# A7105_reference_design.net
KiCad netlist of a schematic drawn in EAGLE
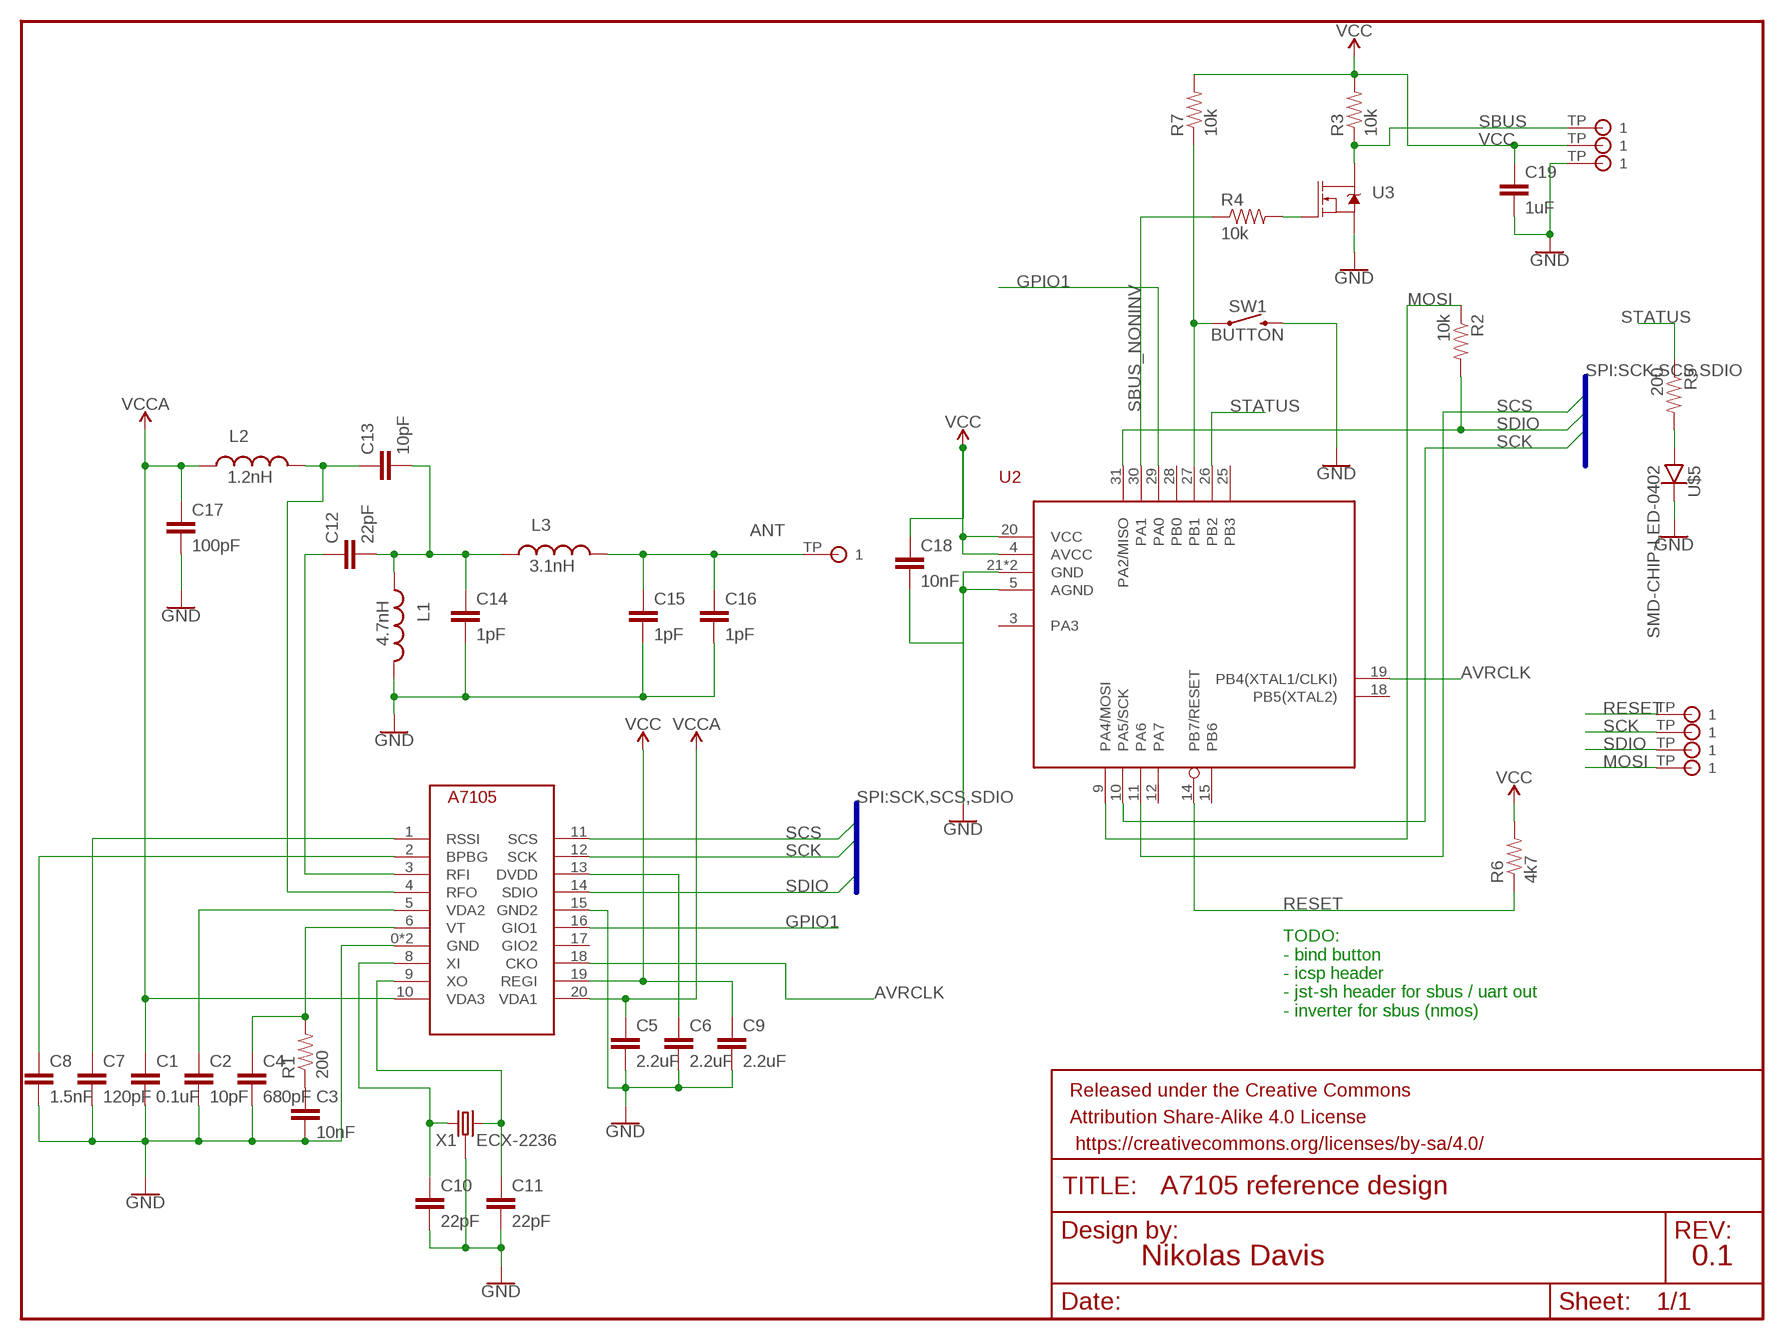
[diagram p0: schematic, sheet 1]

(export (version "E")
  (design (tool "Eeschema 10.0.6"))
  (components
    (comp (ref "ANT")
      (value "TESTPAD")
      (footprint "eagle-import:TESTPAD")
      (libsource (lib "eagle-import") (part "TESTPAD"))
    )
    (comp (ref "C1")
      (value "0.1uF")
      (footprint "eagle-import:0402")
      (libsource (lib "eagle-import") (part "CAP_0402"))
    )
    (comp (ref "C2")
      (value "10pF")
      (footprint "eagle-import:0402")
      (libsource (lib "eagle-import") (part "CAP_0402"))
    )
    (comp (ref "C3")
      (value "10nF")
      (footprint "eagle-import:0402")
      (libsource (lib "eagle-import") (part "CAP_0402"))
    )
    (comp (ref "C4")
      (value "680pF")
      (footprint "eagle-import:0402")
      (libsource (lib "eagle-import") (part "CAP_0402"))
    )
    (comp (ref "C5")
      (value "2.2uF")
      (footprint "eagle-import:0402")
      (libsource (lib "eagle-import") (part "CAP_0402"))
    )
    (comp (ref "C6")
      (value "2.2uF")
      (footprint "eagle-import:0402")
      (libsource (lib "eagle-import") (part "CAP_0402"))
    )
    (comp (ref "C7")
      (value "120pF")
      (footprint "eagle-import:0402")
      (libsource (lib "eagle-import") (part "CAP_0402"))
    )
    (comp (ref "C8")
      (value "1.5nF")
      (footprint "eagle-import:0402")
      (libsource (lib "eagle-import") (part "CAP_0402"))
    )
    (comp (ref "C9")
      (value "2.2uF")
      (footprint "eagle-import:0402")
      (libsource (lib "eagle-import") (part "CAP_0402"))
    )
    (comp (ref "C10")
      (value "22pF")
      (footprint "eagle-import:0402")
      (libsource (lib "eagle-import") (part "CAP_0402"))
    )
    (comp (ref "C11")
      (value "22pF")
      (footprint "eagle-import:0402")
      (libsource (lib "eagle-import") (part "CAP_0402"))
    )
    (comp (ref "C12")
      (value "22pF")
      (footprint "eagle-import:0402")
      (libsource (lib "eagle-import") (part "CAP_0402"))
    )
    (comp (ref "C13")
      (value "10pF")
      (footprint "eagle-import:0402")
      (libsource (lib "eagle-import") (part "CAP_0402"))
    )
    (comp (ref "C14")
      (value "1pF")
      (footprint "eagle-import:0402")
      (libsource (lib "eagle-import") (part "CAP_0402"))
    )
    (comp (ref "C15")
      (value "1pF")
      (footprint "eagle-import:0402")
      (libsource (lib "eagle-import") (part "CAP_0402"))
    )
    (comp (ref "C16")
      (value "1pF")
      (footprint "eagle-import:0402")
      (libsource (lib "eagle-import") (part "CAP_0402"))
    )
    (comp (ref "C17")
      (value "100pF")
      (footprint "eagle-import:0402")
      (libsource (lib "eagle-import") (part "CAP_0402"))
    )
    (comp (ref "C18")
      (value "10nF")
      (footprint "eagle-import:0402")
      (libsource (lib "eagle-import") (part "CAP_0402"))
    )
    (comp (ref "C19")
      (value "1uF")
      (footprint "eagle-import:0402")
      (libsource (lib "eagle-import") (part "CAP_0402"))
    )
    (comp (ref "FRAME1")
      (value "FRAME-LETTER")
      (footprint "eagle-import:CREATIVE_COMMONS")
      (libsource (lib "eagle-import") (part "FRAME-LETTER"))
    )
    (comp (ref "L1")
      (value "4.7nH")
      (footprint "eagle-import:0402")
      (libsource (lib "eagle-import") (part "IND_0402"))
    )
    (comp (ref "L2")
      (value "1.2nH")
      (footprint "eagle-import:0402")
      (libsource (lib "eagle-import") (part "IND_0402"))
    )
    (comp (ref "L3")
      (value "3.1nH")
      (footprint "eagle-import:0402")
      (libsource (lib "eagle-import") (part "IND_0402"))
    )
    (comp (ref "R1")
      (value "200")
      (footprint "eagle-import:0402")
      (libsource (lib "eagle-import") (part "RES_0402"))
    )
    (comp (ref "R2")
      (value "10k")
      (footprint "eagle-import:0402")
      (libsource (lib "eagle-import") (part "RES_0402"))
    )
    (comp (ref "R3")
      (value "10k")
      (footprint "eagle-import:0402")
      (libsource (lib "eagle-import") (part "RES_0402"))
    )
    (comp (ref "R4")
      (value "10k")
      (footprint "eagle-import:0402")
      (libsource (lib "eagle-import") (part "RES_0402"))
    )
    (comp (ref "R5")
      (value "200")
      (footprint "eagle-import:0402")
      (libsource (lib "eagle-import") (part "RES_0402"))
    )
    (comp (ref "R6")
      (value "4k7")
      (footprint "eagle-import:0402")
      (libsource (lib "eagle-import") (part "RES_0402"))
    )
    (comp (ref "R7")
      (value "10k")
      (footprint "eagle-import:0402")
      (libsource (lib "eagle-import") (part "RES_0402"))
    )
    (comp (ref "SW1")
      (value "BUTTON")
      (footprint "eagle-import:PTS-830-SMD-SWITCH")
      (libsource (lib "eagle-import") (part "BUTTON"))
    )
    (comp (ref "U$5")
      (value "SMD-CHIP-LED-0402")
      (footprint "eagle-import:0402LED")
      (libsource (lib "eagle-import") (part "SMD-CHIP-LED-0402"))
    )
    (comp (ref "U$6")
      (value "TESTPAD")
      (footprint "eagle-import:TESTPAD")
      (libsource (lib "eagle-import") (part "TESTPAD"))
    )
    (comp (ref "U$7")
      (value "TESTPAD")
      (footprint "eagle-import:TESTPAD")
      (libsource (lib "eagle-import") (part "TESTPAD"))
    )
    (comp (ref "U$8")
      (value "TESTPAD")
      (footprint "eagle-import:TESTPAD")
      (libsource (lib "eagle-import") (part "TESTPAD"))
    )
    (comp (ref "U$9")
      (value "TESTPAD")
      (footprint "eagle-import:TESTPAD")
      (libsource (lib "eagle-import") (part "TESTPAD"))
    )
    (comp (ref "U$10")
      (value "TESTPAD")
      (footprint "eagle-import:TESTPAD")
      (libsource (lib "eagle-import") (part "TESTPAD"))
    )
    (comp (ref "U$11")
      (value "TESTPAD")
      (footprint "eagle-import:TESTPAD")
      (libsource (lib "eagle-import") (part "TESTPAD"))
    )
    (comp (ref "U$12")
      (value "TESTPAD")
      (footprint "eagle-import:TESTPAD")
      (libsource (lib "eagle-import") (part "TESTPAD"))
    )
    (comp (ref "U1")
      (value "A7105")
      (footprint "eagle-import:QFN20-4X4MM")
      (libsource (lib "eagle-import") (part "A7105"))
    )
    (comp (ref "U2")
      (value "ATTINY167")
      (footprint "eagle-import:VQFN-32")
      (libsource (lib "eagle-import") (part "ATTINY167"))
    )
    (comp (ref "U3")
      (value "NMOSSOT833B/1006")
      (footprint "eagle-import:SOT833B_DFN1006B-3")
      (libsource (lib "eagle-import") (part "NMOSSOT833B/1006"))
    )
    (comp (ref "X1")
      (value "ECX-2236")
      (footprint "eagle-import:2.5X2.0MM_CRYSTAL")
      (libsource (lib "eagle-import") (part "ECX-2236"))
    )
  )
  (nets
    (net (code "2") (name "/ANT") (class "Default")
      (node (ref "ANT") (pin "TP") (pinfunction "1_TP") (pintype "bidirectional"))
      (node (ref "C15") (pin "1") (pinfunction "1_1") (pintype "passive"))
      (node (ref "C16") (pin "1") (pinfunction "1_1") (pintype "passive"))
      (node (ref "L3") (pin "2") (pinfunction "2_2") (pintype "passive"))
    )
    (net (code "3") (name "/AVRCLK") (class "Default")
      (node (ref "U1") (pin "18") (pinfunction "CKO_18") (pintype "bidirectional"))
      (node (ref "U2") (pin "19") (pinfunction "PB4(XTAL1/CLKI)_19") (pintype "bidirectional"))
    )
    (net (code "4") (name "/GPIO1") (class "Default")
      (node (ref "U1") (pin "16") (pinfunction "GIO1_16") (pintype "bidirectional"))
      (node (ref "U2") (pin "29") (pinfunction "PA0_29") (pintype "bidirectional"))
    )
    (net (code "5") (name "/MOSI") (class "Default")
      (node (ref "R2") (pin "1") (pinfunction "1_1") (pintype "passive"))
      (node (ref "U$12") (pin "TP") (pinfunction "1_TP") (pintype "bidirectional"))
      (node (ref "U2") (pin "9") (pinfunction "PA4/MOSI_9") (pintype "bidirectional"))
    )
    (net (code "6") (name "/RESET") (class "Default")
      (node (ref "R6") (pin "1") (pinfunction "1_1") (pintype "passive"))
      (node (ref "U$7") (pin "TP") (pinfunction "1_TP") (pintype "bidirectional"))
      (node (ref "U2") (pin "14") (pinfunction "PB7/RESET_14") (pintype "bidirectional"))
    )
    (net (code "7") (name "/SBUS") (class "Default")
      (node (ref "R3") (pin "1") (pinfunction "1_1") (pintype "passive"))
      (node (ref "U$6") (pin "TP") (pinfunction "1_TP") (pintype "bidirectional"))
      (node (ref "U3") (pin "P$3") (pinfunction "D_P$3") (pintype "bidirectional"))
    )
    (net (code "8") (name "/SBUS_NONINV") (class "Default")
      (node (ref "R4") (pin "1") (pinfunction "1_1") (pintype "passive"))
      (node (ref "U2") (pin "30") (pinfunction "PA1_30") (pintype "bidirectional"))
    )
    (net (code "9") (name "/SCK") (class "Default")
      (node (ref "U$10") (pin "TP") (pinfunction "1_TP") (pintype "bidirectional"))
      (node (ref "U1") (pin "12") (pinfunction "SCK_12") (pintype "bidirectional"))
      (node (ref "U2") (pin "10") (pinfunction "PA5/SCK_10") (pintype "bidirectional"))
    )
    (net (code "10") (name "/SCS") (class "Default")
      (node (ref "U1") (pin "11") (pinfunction "SCS_11") (pintype "bidirectional"))
      (node (ref "U2") (pin "11") (pinfunction "PA6_11") (pintype "bidirectional"))
    )
    (net (code "11") (name "/SDIO") (class "Default")
      (node (ref "R2") (pin "2") (pinfunction "2_2") (pintype "passive"))
      (node (ref "U$11") (pin "TP") (pinfunction "1_TP") (pintype "bidirectional"))
      (node (ref "U1") (pin "14") (pinfunction "SDIO_14") (pintype "bidirectional"))
      (node (ref "U2") (pin "31") (pinfunction "PA2/MISO_31") (pintype "bidirectional"))
    )
    (net (code "12") (name "/STATUS") (class "Default")
      (node (ref "R5") (pin "1") (pinfunction "1_1") (pintype "passive"))
      (node (ref "U2") (pin "26") (pinfunction "PB2_26") (pintype "bidirectional"))
    )
    (net (code "14") (name "GND") (class "Default")
      (node (ref "C1") (pin "2") (pinfunction "2_2") (pintype "passive"))
      (node (ref "C10") (pin "2") (pinfunction "2_2") (pintype "passive"))
      (node (ref "C11") (pin "2") (pinfunction "2_2") (pintype "passive"))
      (node (ref "C14") (pin "2") (pinfunction "2_2") (pintype "passive"))
      (node (ref "C15") (pin "2") (pinfunction "2_2") (pintype "passive"))
      (node (ref "C16") (pin "2") (pinfunction "2_2") (pintype "passive"))
      (node (ref "C17") (pin "2") (pinfunction "2_2") (pintype "passive"))
      (node (ref "C18") (pin "2") (pinfunction "2_2") (pintype "passive"))
      (node (ref "C19") (pin "2") (pinfunction "2_2") (pintype "passive"))
      (node (ref "C2") (pin "2") (pinfunction "2_2") (pintype "passive"))
      (node (ref "C3") (pin "2") (pinfunction "2_2") (pintype "passive"))
      (node (ref "C4") (pin "2") (pinfunction "2_2") (pintype "passive"))
      (node (ref "C5") (pin "2") (pinfunction "2_2") (pintype "passive"))
      (node (ref "C6") (pin "2") (pinfunction "2_2") (pintype "passive"))
      (node (ref "C7") (pin "2") (pinfunction "2_2") (pintype "passive"))
      (node (ref "C8") (pin "2") (pinfunction "2_2") (pintype "passive"))
      (node (ref "C9") (pin "2") (pinfunction "2_2") (pintype "passive"))
      (node (ref "L1") (pin "2") (pinfunction "2_2") (pintype "passive"))
      (node (ref "SW1") (pin "P$3") (pinfunction "2_P$3") (pintype "passive"))
      (node (ref "SW1") (pin "P$4") (pinfunction "2_P$4") (pintype "passive"))
      (node (ref "U$5") (pin "1") (pinfunction "C_1") (pintype "passive"))
      (node (ref "U$9") (pin "TP") (pinfunction "1_TP") (pintype "bidirectional"))
      (node (ref "U1") (pin "0") (pinfunction "GND_0") (pintype "bidirectional"))
      (node (ref "U1") (pin "15") (pinfunction "GND2_15") (pintype "bidirectional"))
      (node (ref "U1") (pin "7") (pinfunction "GND_7") (pintype "bidirectional"))
      (node (ref "U2") (pin "21") (pinfunction "GND_21") (pintype "bidirectional"))
      (node (ref "U2") (pin "5") (pinfunction "AGND_5") (pintype "bidirectional"))
      (node (ref "U2") (pin "PAD") (pinfunction "GND_PAD") (pintype "bidirectional"))
      (node (ref "U3") (pin "P$2") (pinfunction "S_P$2") (pintype "bidirectional"))
      (node (ref "X1") (pin "P$2") (pinfunction "3_P$2") (pintype "passive"))
      (node (ref "X1") (pin "P$4") (pinfunction "3_P$4") (pintype "passive"))
    )
    (net (code "15") (name "Net-(C3-Pad1)") (class "Default")
      (node (ref "C3") (pin "1") (pinfunction "1_1") (pintype "passive"))
      (node (ref "R1") (pin "1") (pinfunction "1_1") (pintype "passive"))
    )
    (net (code "16") (name "Net-(C12-Pad2)") (class "Default")
      (node (ref "C12") (pin "2") (pinfunction "2_2") (pintype "passive"))
      (node (ref "C13") (pin "2") (pinfunction "2_2") (pintype "passive"))
      (node (ref "C14") (pin "1") (pinfunction "1_1") (pintype "passive"))
      (node (ref "L1") (pin "1") (pinfunction "1_1") (pintype "passive"))
      (node (ref "L3") (pin "1") (pinfunction "1_1") (pintype "passive"))
    )
    (net (code "17") (name "Net-(U$5-A)") (class "Default")
      (node (ref "R5") (pin "2") (pinfunction "2_2") (pintype "passive"))
      (node (ref "U$5") (pin "2") (pinfunction "A_2") (pintype "passive"))
    )
    (net (code "18") (name "Net-(U1-BPBG)") (class "Default")
      (node (ref "C8") (pin "1") (pinfunction "1_1") (pintype "passive"))
      (node (ref "U1") (pin "2") (pinfunction "BPBG_2") (pintype "bidirectional"))
    )
    (net (code "19") (name "Net-(U1-DVDD)") (class "Default")
      (node (ref "C6") (pin "1") (pinfunction "1_1") (pintype "passive"))
      (node (ref "U1") (pin "13") (pinfunction "DVDD_13") (pintype "bidirectional"))
    )
    (net (code "20") (name "Net-(U1-RFI)") (class "Default")
      (node (ref "C12") (pin "1") (pinfunction "1_1") (pintype "passive"))
      (node (ref "U1") (pin "3") (pinfunction "RFI_3") (pintype "bidirectional"))
    )
    (net (code "21") (name "Net-(U1-RFO)") (class "Default")
      (node (ref "C13") (pin "1") (pinfunction "1_1") (pintype "passive"))
      (node (ref "L2") (pin "2") (pinfunction "2_2") (pintype "passive"))
      (node (ref "U1") (pin "4") (pinfunction "RFO_4") (pintype "bidirectional"))
    )
    (net (code "22") (name "Net-(U1-RSSI)") (class "Default")
      (node (ref "C7") (pin "1") (pinfunction "1_1") (pintype "passive"))
      (node (ref "U1") (pin "1") (pinfunction "RSSI_1") (pintype "bidirectional"))
    )
    (net (code "23") (name "Net-(U1-VDA2)") (class "Default")
      (node (ref "C2") (pin "1") (pinfunction "1_1") (pintype "passive"))
      (node (ref "U1") (pin "5") (pinfunction "VDA2_5") (pintype "bidirectional"))
    )
    (net (code "24") (name "Net-(U1-VT)") (class "Default")
      (node (ref "C4") (pin "1") (pinfunction "1_1") (pintype "passive"))
      (node (ref "R1") (pin "2") (pinfunction "2_2") (pintype "passive"))
      (node (ref "U1") (pin "6") (pinfunction "VT_6") (pintype "bidirectional"))
    )
    (net (code "25") (name "Net-(U1-XI)") (class "Default")
      (node (ref "C10") (pin "1") (pinfunction "1_1") (pintype "passive"))
      (node (ref "U1") (pin "8") (pinfunction "XI_8") (pintype "bidirectional"))
      (node (ref "X1") (pin "P$1") (pinfunction "1_P$1") (pintype "passive"))
    )
    (net (code "26") (name "Net-(U1-XO)") (class "Default")
      (node (ref "C11") (pin "1") (pinfunction "1_1") (pintype "passive"))
      (node (ref "U1") (pin "9") (pinfunction "XO_9") (pintype "bidirectional"))
      (node (ref "X1") (pin "P$3") (pinfunction "2_P$3") (pintype "passive"))
    )
    (net (code "27") (name "Net-(U2-PB1)") (class "Default")
      (node (ref "R7") (pin "1") (pinfunction "1_1") (pintype "passive"))
      (node (ref "SW1") (pin "P$1") (pinfunction "1_P$1") (pintype "passive"))
      (node (ref "SW1") (pin "P$2") (pinfunction "1_P$2") (pintype "passive"))
      (node (ref "U2") (pin "27") (pinfunction "PB1_27") (pintype "bidirectional"))
    )
    (net (code "28") (name "Net-(U3-G)") (class "Default")
      (node (ref "R4") (pin "2") (pinfunction "2_2") (pintype "passive"))
      (node (ref "U3") (pin "P$1") (pinfunction "G_P$1") (pintype "bidirectional"))
    )
    (net (code "29") (name "VCC") (class "Default")
      (node (ref "C18") (pin "1") (pinfunction "1_1") (pintype "passive"))
      (node (ref "C19") (pin "1") (pinfunction "1_1") (pintype "passive"))
      (node (ref "C9") (pin "1") (pinfunction "1_1") (pintype "passive"))
      (node (ref "R3") (pin "2") (pinfunction "2_2") (pintype "passive"))
      (node (ref "R6") (pin "2") (pinfunction "2_2") (pintype "passive"))
      (node (ref "R7") (pin "2") (pinfunction "2_2") (pintype "passive"))
      (node (ref "U$8") (pin "TP") (pinfunction "1_TP") (pintype "bidirectional"))
      (node (ref "U1") (pin "19") (pinfunction "REGI_19") (pintype "bidirectional"))
      (node (ref "U2") (pin "20") (pinfunction "VCC_20") (pintype "bidirectional"))
      (node (ref "U2") (pin "4") (pinfunction "AVCC_4") (pintype "bidirectional"))
    )
    (net (code "30") (name "VCCA") (class "Default")
      (node (ref "C1") (pin "1") (pinfunction "1_1") (pintype "passive"))
      (node (ref "C17") (pin "1") (pinfunction "1_1") (pintype "passive"))
      (node (ref "C5") (pin "1") (pinfunction "1_1") (pintype "passive"))
      (node (ref "L2") (pin "1") (pinfunction "1_1") (pintype "passive"))
      (node (ref "U1") (pin "10") (pinfunction "VDA3_10") (pintype "bidirectional"))
      (node (ref "U1") (pin "20") (pinfunction "VDA1_20") (pintype "bidirectional"))
    )
    (net (code "31") (name "unconnected-(U1-GIO2-Pad17)") (class "Default")
      (node (ref "U1") (pin "17") (pinfunction "GIO2_17") (pintype "bidirectional"))
    )
    (net (code "32") (name "unconnected-(U2-PA3-Pad3)") (class "Default")
      (node (ref "U2") (pin "3") (pinfunction "PA3_3") (pintype "bidirectional"))
    )
    (net (code "33") (name "unconnected-(U2-PA7-Pad12)") (class "Default")
      (node (ref "U2") (pin "12") (pinfunction "PA7_12") (pintype "bidirectional"))
    )
    (net (code "34") (name "unconnected-(U2-PB0-Pad28)") (class "Default")
      (node (ref "U2") (pin "28") (pinfunction "PB0_28") (pintype "bidirectional"))
    )
    (net (code "35") (name "unconnected-(U2-PB3-Pad25)") (class "Default")
      (node (ref "U2") (pin "25") (pinfunction "PB3_25") (pintype "bidirectional"))
    )
    (net (code "36") (name "unconnected-(U2-PB5(XTAL2)-Pad18)") (class "Default")
      (node (ref "U2") (pin "18") (pinfunction "PB5(XTAL2)_18") (pintype "bidirectional"))
    )
    (net (code "37") (name "unconnected-(U2-PB6-Pad15)") (class "Default")
      (node (ref "U2") (pin "15") (pinfunction "PB6_15") (pintype "bidirectional"))
    )
  )
)
